# stm32f103rct6v1.net
KiCad netlist of a schematic drawn in EasyEDA Pro
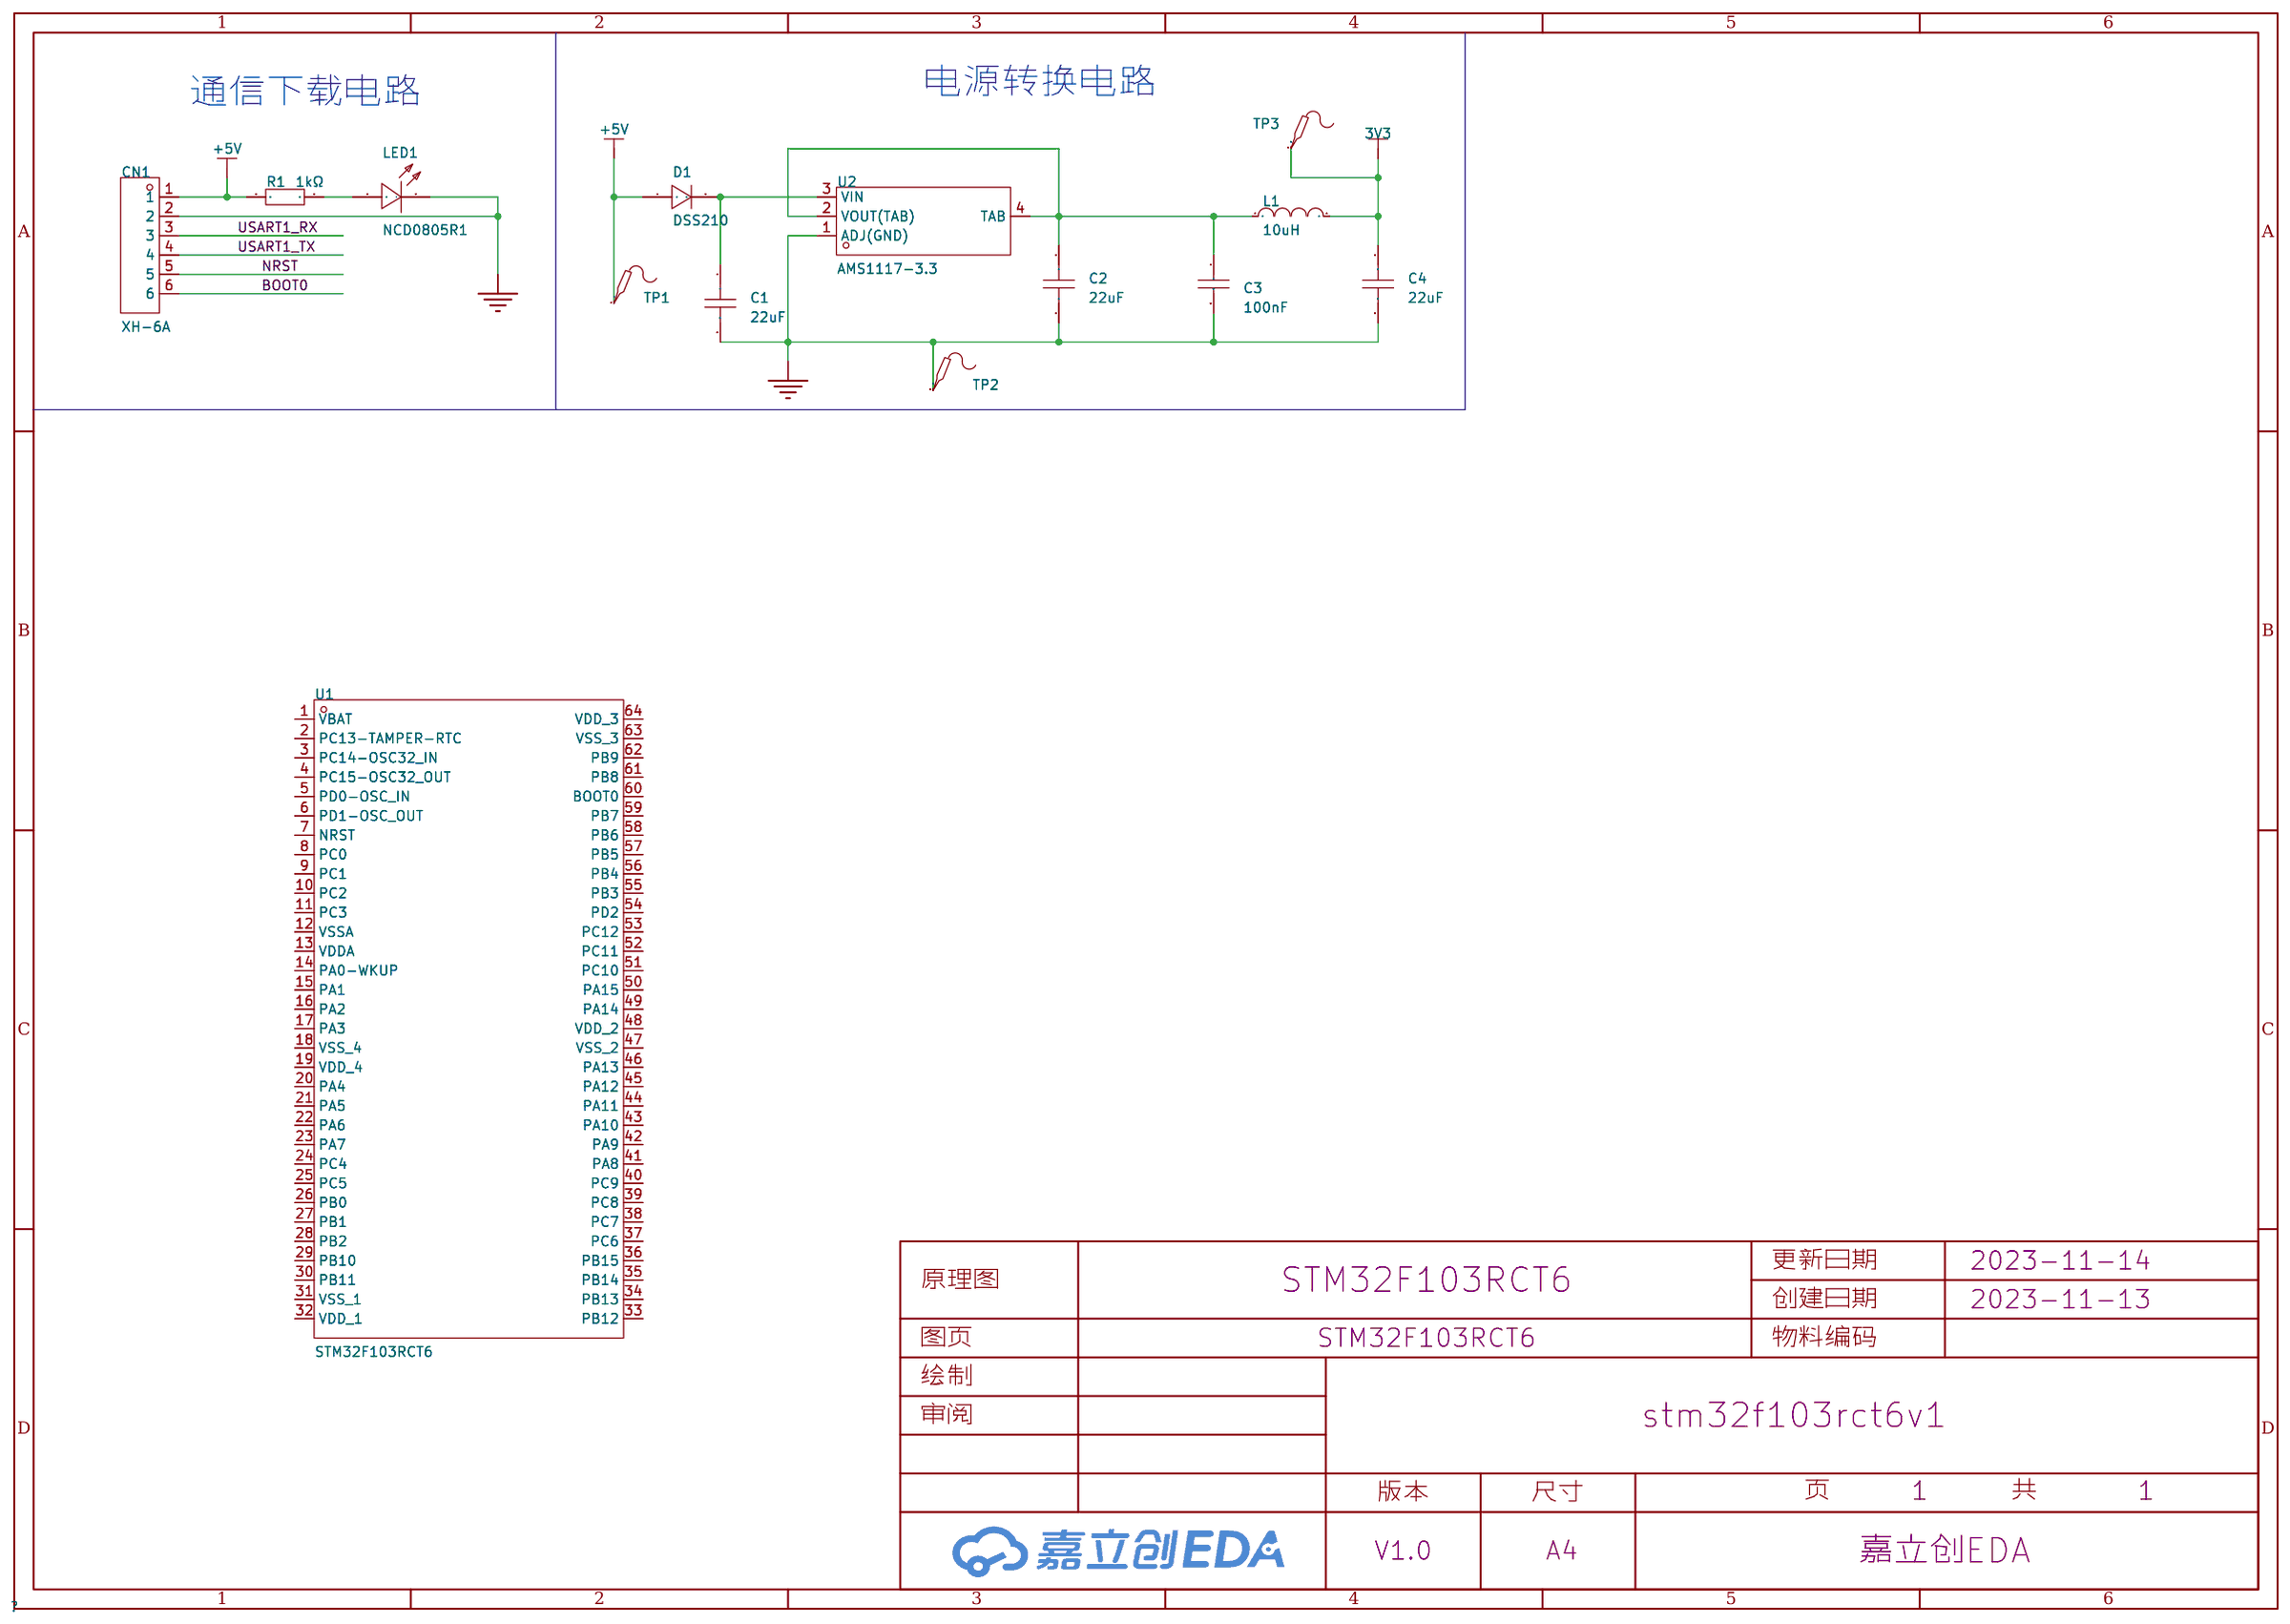
[diagram p0: schematic sheet]

(export (version "E")
  (design (tool "Eeschema 10.0.6"))
  (components
    (comp (ref "C1")
      (value "22uF")
      (footprint "easyedapro:C0805")
      (description "容值:22uF;精度:±20%;额定电压:25V;材质(温度系数):X5R;")
      (fields
        (field (name "Manufacturer Part") "CL21A226MAYNNNE")
        (field (name "Manufacturer") "SAMSUNG(三星)")
      )
      (libsource (lib "easyedapro") (part "CL21A226MAYNNNE"))
    )
    (comp (ref "C2")
      (value "22uF")
      (footprint "easyedapro:C0805")
      (description "容值:22uF;精度:±20%;额定电压:25V;材质(温度系数):X5R;")
      (fields
        (field (name "Manufacturer Part") "CL21A226MAYNNNE")
        (field (name "Manufacturer") "SAMSUNG(三星)")
      )
      (libsource (lib "easyedapro") (part "CL21A226MAYNNNE"))
    )
    (comp (ref "C3")
      (value "100nF")
      (footprint "easyedapro:C0603")
      (description "容值:100nF;精度:±10%;额定电压:50V;材质(温度系数):X7R;")
      (fields (field (name "Manufacturer Part") "0603B104K500NT") (field (name "Manufacturer") "FH(风华)"))
      (libsource (lib "easyedapro") (part "0603B104K500NT"))
    )
    (comp (ref "C4")
      (value "22uF")
      (footprint "easyedapro:C0805")
      (description "容值:22uF;精度:±20%;额定电压:25V;材质(温度系数):X5R;")
      (fields
        (field (name "Manufacturer Part") "CL21A226MAYNNNE")
        (field (name "Manufacturer") "SAMSUNG(三星)")
      )
      (libsource (lib "easyedapro") (part "CL21A226MAYNNNE"))
    )
    (comp (ref "CN1")
      (value "XH-6A")
      (footprint "easyedapro:CONN-TH_6P-P2.50_HCTL_XH-6A_C2908604")
      (description "插针结构:1x6P;间距:2.5mm;公母:公;安装方式:直插;行距:-;排数:1;每排PIN数:6;参考系列:XH;额定电流:3A;工作温度范围:-25°C~+85°C;")
      (fields (field (name "Manufacturer") "HCTL(华灿天禄)"))
      (libsource (lib "easyedapro") (part "XH-6A_C2908604"))
    )
    (comp (ref "D1")
      (value "DSS210")
      (footprint "easyedapro:SOD-123_L2.8-W1.8-LS3.7-FD")
      (description "正向压降(Vf):850mV@2A;直流反向耐压(Vr):100V;平均整流电流(Io):2A;")
      (fields (field (name "Manufacturer") "BORN(伯恩半导体)"))
      (libsource (lib "easyedapro") (part "DSS210"))
    )
    (comp (ref "L1")
      (value "10uH")
      (footprint "easyedapro:IND-SMD_L7.3-W6.8")
      (description "电感值:10uH;精度:±20%;额定电流:4.5A;类型:一体成型电感;饱和电流(Isat):5.5A;")
      (fields (field (name "Manufacturer Part") "FXL0630-100-M") (field (name "Manufacturer") "cjiang(长江微电)"))
      (libsource (lib "easyedapro") (part "FXL0630-100-M"))
    )
    (comp (ref "LED1")
      (value "NCD0805R1")
      (footprint "easyedapro:LED0805-R-RD")
      (fields (field (name "Manufacturer") "国星光电"))
      (libsource (lib "easyedapro") (part "FC-2012HRK-620D"))
    )
    (comp (ref "R1")
      (value "1kΩ")
      (footprint "easyedapro:R0603")
      (description "阻值:1kΩ;精度:±1%;功率:100mW;温度系数:±100ppm/°C;电阻类型:厚膜电阻;")
      (fields
        (field (name "Manufacturer Part") "0603WAF1001T5E")
        (field (name "Manufacturer") "UNI-ROYAL(厚声)")
      )
      (libsource (lib "easyedapro") (part "0603WAF1001T5E"))
    )
    (comp (ref "TP1")
      (value "~")
      (footprint "easyedapro:Test-Point-0.5mm")
      (description "Test Point 测试点")
      (libsource (lib "easyedapro") (part "Test-Point"))
    )
    (comp (ref "TP2")
      (value "~")
      (footprint "easyedapro:Test-Point-0.5mm")
      (description "Test Point 测试点")
      (libsource (lib "easyedapro") (part "Test-Point"))
    )
    (comp (ref "TP3")
      (value "~")
      (footprint "easyedapro:Test-Point-0.5mm")
      (description "Test Point 测试点")
      (libsource (lib "easyedapro") (part "Test-Point"))
    )
    (comp (ref "U1")
      (value "STM32F103RCT6")
      (footprint "easyedapro:LQFP-64_L10.0-W10.0-P0.50-LS12.0-BL")
      (fields (field (name "Manufacturer") "ST(意法半导体)"))
      (libsource (lib "easyedapro") (part "STM32F103RCT6"))
    )
    (comp (ref "U2")
      (value "AMS1117-3.3")
      (footprint "easyedapro:SOT-223-4_L6.5-W3.5-P2.30-LS7.0-BR")
      (description "输出类型:固定;最大输入电压:18V;输出电压:3.3V;输出电流:1A;电源纹波抑制比(PSRR):60dB@(120Hz);输出极性:正;")
      (fields (field (name "Manufacturer") "UMW(友台半导体)"))
      (libsource (lib "easyedapro") (part "AMS1117-3.3_C347222"))
    )
  )
  (nets
    (net (code "1") (name "+5V") (class "Default")
      (node (ref "CN1") (pin "1") (pinfunction "1_1") (pintype "unspecified"))
      (node (ref "D1") (pin "1") (pinfunction "A_1") (pintype "unspecified"))
      (node (ref "R1") (pin "1") (pinfunction "1_1") (pintype "input"))
      (node (ref "TP1") (pin "1") (pinfunction "1_1") (pintype "input"))
    )
    (net (code "2") (name "/BOOT0") (class "Default")
      (node (ref "CN1") (pin "6") (pinfunction "6_6") (pintype "unspecified"))
    )
    (net (code "3") (name "/NRST") (class "Default")
      (node (ref "CN1") (pin "5") (pinfunction "5_5") (pintype "unspecified"))
    )
    (net (code "4") (name "/USART1_RX") (class "Default")
      (node (ref "CN1") (pin "3") (pinfunction "3_3") (pintype "unspecified"))
    )
    (net (code "5") (name "/USART1_TX") (class "Default")
      (node (ref "CN1") (pin "4") (pinfunction "4_4") (pintype "unspecified"))
    )
    (net (code "6") (name "3V3") (class "Default")
      (node (ref "C4") (pin "1") (pinfunction "1_1") (pintype "input"))
      (node (ref "L1") (pin "2") (pinfunction "2_2") (pintype "unspecified"))
      (node (ref "TP3") (pin "1") (pinfunction "1_1") (pintype "input"))
    )
    (net (code "7") (name "GND") (class "Default")
      (node (ref "C1") (pin "2") (pinfunction "2_2") (pintype "input"))
      (node (ref "C2") (pin "2") (pinfunction "2_2") (pintype "input"))
      (node (ref "C3") (pin "2") (pinfunction "2_2") (pintype "input"))
      (node (ref "C4") (pin "2") (pinfunction "2_2") (pintype "input"))
      (node (ref "CN1") (pin "2") (pinfunction "2_2") (pintype "unspecified"))
      (node (ref "LED1") (pin "2") (pinfunction "-_2") (pintype "unspecified"))
      (node (ref "TP2") (pin "1") (pinfunction "1_1") (pintype "input"))
      (node (ref "U2") (pin "1") (pinfunction "ADJ(GND)_1") (pintype "unspecified"))
    )
    (net (code "8") (name "Net-(D1-K)") (class "Default")
      (node (ref "C1") (pin "1") (pinfunction "1_1") (pintype "input"))
      (node (ref "D1") (pin "2") (pinfunction "K_2") (pintype "unspecified"))
      (node (ref "U2") (pin "3") (pinfunction "VIN_3") (pintype "unspecified"))
    )
    (net (code "9") (name "Net-(LED1-+)") (class "Default")
      (node (ref "LED1") (pin "1") (pinfunction "+_1") (pintype "unspecified"))
      (node (ref "R1") (pin "2") (pinfunction "2_2") (pintype "input"))
    )
    (net (code "10") (name "Net-(U2-TAB)") (class "Default")
      (node (ref "C2") (pin "1") (pinfunction "1_1") (pintype "input"))
      (node (ref "C3") (pin "1") (pinfunction "1_1") (pintype "input"))
      (node (ref "L1") (pin "1") (pinfunction "1_1") (pintype "unspecified"))
      (node (ref "U2") (pin "2") (pinfunction "VOUT(TAB)_2") (pintype "unspecified"))
      (node (ref "U2") (pin "4") (pinfunction "TAB_4") (pintype "unspecified"))
    )
    (net (code "11") (name "unconnected-(U1-BOOT0-Pad60)") (class "Default")
      (node (ref "U1") (pin "60") (pinfunction "BOOT0_60") (pintype "unspecified"))
    )
    (net (code "12") (name "unconnected-(U1-NRST-Pad7)") (class "Default")
      (node (ref "U1") (pin "7") (pinfunction "NRST_7") (pintype "unspecified"))
    )
    (net (code "13") (name "unconnected-(U1-PA0-WKUP-Pad14)") (class "Default")
      (node (ref "U1") (pin "14") (pinfunction "PA0-WKUP_14") (pintype "unspecified"))
    )
    (net (code "14") (name "unconnected-(U1-PA1-Pad15)") (class "Default")
      (node (ref "U1") (pin "15") (pinfunction "PA1_15") (pintype "unspecified"))
    )
    (net (code "15") (name "unconnected-(U1-PA2-Pad16)") (class "Default")
      (node (ref "U1") (pin "16") (pinfunction "PA2_16") (pintype "unspecified"))
    )
    (net (code "16") (name "unconnected-(U1-PA3-Pad17)") (class "Default")
      (node (ref "U1") (pin "17") (pinfunction "PA3_17") (pintype "unspecified"))
    )
    (net (code "17") (name "unconnected-(U1-PA4-Pad20)") (class "Default")
      (node (ref "U1") (pin "20") (pinfunction "PA4_20") (pintype "unspecified"))
    )
    (net (code "18") (name "unconnected-(U1-PA5-Pad21)") (class "Default")
      (node (ref "U1") (pin "21") (pinfunction "PA5_21") (pintype "unspecified"))
    )
    (net (code "19") (name "unconnected-(U1-PA6-Pad22)") (class "Default")
      (node (ref "U1") (pin "22") (pinfunction "PA6_22") (pintype "unspecified"))
    )
    (net (code "20") (name "unconnected-(U1-PA7-Pad23)") (class "Default")
      (node (ref "U1") (pin "23") (pinfunction "PA7_23") (pintype "unspecified"))
    )
    (net (code "21") (name "unconnected-(U1-PA8-Pad41)") (class "Default")
      (node (ref "U1") (pin "41") (pinfunction "PA8_41") (pintype "unspecified"))
    )
    (net (code "22") (name "unconnected-(U1-PA9-Pad42)") (class "Default")
      (node (ref "U1") (pin "42") (pinfunction "PA9_42") (pintype "unspecified"))
    )
    (net (code "23") (name "unconnected-(U1-PA10-Pad43)") (class "Default")
      (node (ref "U1") (pin "43") (pinfunction "PA10_43") (pintype "unspecified"))
    )
    (net (code "24") (name "unconnected-(U1-PA11-Pad44)") (class "Default")
      (node (ref "U1") (pin "44") (pinfunction "PA11_44") (pintype "unspecified"))
    )
    (net (code "25") (name "unconnected-(U1-PA12-Pad45)") (class "Default")
      (node (ref "U1") (pin "45") (pinfunction "PA12_45") (pintype "unspecified"))
    )
    (net (code "26") (name "unconnected-(U1-PA13-Pad46)") (class "Default")
      (node (ref "U1") (pin "46") (pinfunction "PA13_46") (pintype "unspecified"))
    )
    (net (code "27") (name "unconnected-(U1-PA14-Pad49)") (class "Default")
      (node (ref "U1") (pin "49") (pinfunction "PA14_49") (pintype "unspecified"))
    )
    (net (code "28") (name "unconnected-(U1-PA15-Pad50)") (class "Default")
      (node (ref "U1") (pin "50") (pinfunction "PA15_50") (pintype "unspecified"))
    )
    (net (code "29") (name "unconnected-(U1-PB0-Pad26)") (class "Default")
      (node (ref "U1") (pin "26") (pinfunction "PB0_26") (pintype "unspecified"))
    )
    (net (code "30") (name "unconnected-(U1-PB1-Pad27)") (class "Default")
      (node (ref "U1") (pin "27") (pinfunction "PB1_27") (pintype "unspecified"))
    )
    (net (code "31") (name "unconnected-(U1-PB2-Pad28)") (class "Default")
      (node (ref "U1") (pin "28") (pinfunction "PB2_28") (pintype "unspecified"))
    )
    (net (code "32") (name "unconnected-(U1-PB3-Pad55)") (class "Default")
      (node (ref "U1") (pin "55") (pinfunction "PB3_55") (pintype "unspecified"))
    )
    (net (code "33") (name "unconnected-(U1-PB4-Pad56)") (class "Default")
      (node (ref "U1") (pin "56") (pinfunction "PB4_56") (pintype "unspecified"))
    )
    (net (code "34") (name "unconnected-(U1-PB5-Pad57)") (class "Default")
      (node (ref "U1") (pin "57") (pinfunction "PB5_57") (pintype "unspecified"))
    )
    (net (code "35") (name "unconnected-(U1-PB6-Pad58)") (class "Default")
      (node (ref "U1") (pin "58") (pinfunction "PB6_58") (pintype "unspecified"))
    )
    (net (code "36") (name "unconnected-(U1-PB7-Pad59)") (class "Default")
      (node (ref "U1") (pin "59") (pinfunction "PB7_59") (pintype "unspecified"))
    )
    (net (code "37") (name "unconnected-(U1-PB8-Pad61)") (class "Default")
      (node (ref "U1") (pin "61") (pinfunction "PB8_61") (pintype "unspecified"))
    )
    (net (code "38") (name "unconnected-(U1-PB9-Pad62)") (class "Default")
      (node (ref "U1") (pin "62") (pinfunction "PB9_62") (pintype "unspecified"))
    )
    (net (code "39") (name "unconnected-(U1-PB10-Pad29)") (class "Default")
      (node (ref "U1") (pin "29") (pinfunction "PB10_29") (pintype "unspecified"))
    )
    (net (code "40") (name "unconnected-(U1-PB11-Pad30)") (class "Default")
      (node (ref "U1") (pin "30") (pinfunction "PB11_30") (pintype "unspecified"))
    )
    (net (code "41") (name "unconnected-(U1-PB12-Pad33)") (class "Default")
      (node (ref "U1") (pin "33") (pinfunction "PB12_33") (pintype "unspecified"))
    )
    (net (code "42") (name "unconnected-(U1-PB13-Pad34)") (class "Default")
      (node (ref "U1") (pin "34") (pinfunction "PB13_34") (pintype "unspecified"))
    )
    (net (code "43") (name "unconnected-(U1-PB14-Pad35)") (class "Default")
      (node (ref "U1") (pin "35") (pinfunction "PB14_35") (pintype "unspecified"))
    )
    (net (code "44") (name "unconnected-(U1-PB15-Pad36)") (class "Default")
      (node (ref "U1") (pin "36") (pinfunction "PB15_36") (pintype "unspecified"))
    )
    (net (code "45") (name "unconnected-(U1-PC0-Pad8)") (class "Default")
      (node (ref "U1") (pin "8") (pinfunction "PC0_8") (pintype "unspecified"))
    )
    (net (code "46") (name "unconnected-(U1-PC1-Pad9)") (class "Default")
      (node (ref "U1") (pin "9") (pinfunction "PC1_9") (pintype "unspecified"))
    )
    (net (code "47") (name "unconnected-(U1-PC2-Pad10)") (class "Default")
      (node (ref "U1") (pin "10") (pinfunction "PC2_10") (pintype "unspecified"))
    )
    (net (code "48") (name "unconnected-(U1-PC3-Pad11)") (class "Default")
      (node (ref "U1") (pin "11") (pinfunction "PC3_11") (pintype "unspecified"))
    )
    (net (code "49") (name "unconnected-(U1-PC4-Pad24)") (class "Default")
      (node (ref "U1") (pin "24") (pinfunction "PC4_24") (pintype "unspecified"))
    )
    (net (code "50") (name "unconnected-(U1-PC5-Pad25)") (class "Default")
      (node (ref "U1") (pin "25") (pinfunction "PC5_25") (pintype "unspecified"))
    )
    (net (code "51") (name "unconnected-(U1-PC6-Pad37)") (class "Default")
      (node (ref "U1") (pin "37") (pinfunction "PC6_37") (pintype "unspecified"))
    )
    (net (code "52") (name "unconnected-(U1-PC7-Pad38)") (class "Default")
      (node (ref "U1") (pin "38") (pinfunction "PC7_38") (pintype "unspecified"))
    )
    (net (code "53") (name "unconnected-(U1-PC8-Pad39)") (class "Default")
      (node (ref "U1") (pin "39") (pinfunction "PC8_39") (pintype "unspecified"))
    )
    (net (code "54") (name "unconnected-(U1-PC9-Pad40)") (class "Default")
      (node (ref "U1") (pin "40") (pinfunction "PC9_40") (pintype "unspecified"))
    )
    (net (code "55") (name "unconnected-(U1-PC10-Pad51)") (class "Default")
      (node (ref "U1") (pin "51") (pinfunction "PC10_51") (pintype "unspecified"))
    )
    (net (code "56") (name "unconnected-(U1-PC11-Pad52)") (class "Default")
      (node (ref "U1") (pin "52") (pinfunction "PC11_52") (pintype "unspecified"))
    )
    (net (code "57") (name "unconnected-(U1-PC12-Pad53)") (class "Default")
      (node (ref "U1") (pin "53") (pinfunction "PC12_53") (pintype "unspecified"))
    )
    (net (code "58") (name "unconnected-(U1-PC13-TAMPER-RTC-Pad2)") (class "Default")
      (node (ref "U1") (pin "2") (pinfunction "PC13-TAMPER-RTC_2") (pintype "unspecified"))
    )
    (net (code "59") (name "unconnected-(U1-PC14-OSC32_IN-Pad3)") (class "Default")
      (node (ref "U1") (pin "3") (pinfunction "PC14-OSC32_IN_3") (pintype "unspecified"))
    )
    (net (code "60") (name "unconnected-(U1-PC15-OSC32_OUT-Pad4)") (class "Default")
      (node (ref "U1") (pin "4") (pinfunction "PC15-OSC32_OUT_4") (pintype "unspecified"))
    )
    (net (code "61") (name "unconnected-(U1-PD0-OSC_IN-Pad5)") (class "Default")
      (node (ref "U1") (pin "5") (pinfunction "PD0-OSC_IN_5") (pintype "unspecified"))
    )
    (net (code "62") (name "unconnected-(U1-PD1-OSC_OUT-Pad6)") (class "Default")
      (node (ref "U1") (pin "6") (pinfunction "PD1-OSC_OUT_6") (pintype "unspecified"))
    )
    (net (code "63") (name "unconnected-(U1-PD2-Pad54)") (class "Default")
      (node (ref "U1") (pin "54") (pinfunction "PD2_54") (pintype "unspecified"))
    )
    (net (code "64") (name "unconnected-(U1-VBAT-Pad1)") (class "Default")
      (node (ref "U1") (pin "1") (pinfunction "VBAT_1") (pintype "unspecified"))
    )
    (net (code "65") (name "unconnected-(U1-VDDA-Pad13)") (class "Default")
      (node (ref "U1") (pin "13") (pinfunction "VDDA_13") (pintype "unspecified"))
    )
    (net (code "66") (name "unconnected-(U1-VDD_1-Pad32)") (class "Default")
      (node (ref "U1") (pin "32") (pinfunction "VDD_1_32") (pintype "unspecified"))
    )
    (net (code "67") (name "unconnected-(U1-VDD_2-Pad48)") (class "Default")
      (node (ref "U1") (pin "48") (pinfunction "VDD_2_48") (pintype "unspecified"))
    )
    (net (code "68") (name "unconnected-(U1-VDD_3-Pad64)") (class "Default")
      (node (ref "U1") (pin "64") (pinfunction "VDD_3_64") (pintype "unspecified"))
    )
    (net (code "69") (name "unconnected-(U1-VDD_4-Pad19)") (class "Default")
      (node (ref "U1") (pin "19") (pinfunction "VDD_4_19") (pintype "unspecified"))
    )
    (net (code "70") (name "unconnected-(U1-VSSA-Pad12)") (class "Default")
      (node (ref "U1") (pin "12") (pinfunction "VSSA_12") (pintype "unspecified"))
    )
    (net (code "71") (name "unconnected-(U1-VSS_1-Pad31)") (class "Default")
      (node (ref "U1") (pin "31") (pinfunction "VSS_1_31") (pintype "unspecified"))
    )
    (net (code "72") (name "unconnected-(U1-VSS_2-Pad47)") (class "Default")
      (node (ref "U1") (pin "47") (pinfunction "VSS_2_47") (pintype "unspecified"))
    )
    (net (code "73") (name "unconnected-(U1-VSS_3-Pad63)") (class "Default")
      (node (ref "U1") (pin "63") (pinfunction "VSS_3_63") (pintype "unspecified"))
    )
    (net (code "74") (name "unconnected-(U1-VSS_4-Pad18)") (class "Default")
      (node (ref "U1") (pin "18") (pinfunction "VSS_4_18") (pintype "unspecified"))
    )
  )
)
